# ESP32.net
KiCad netlist of a schematic drawn in Altium Designer
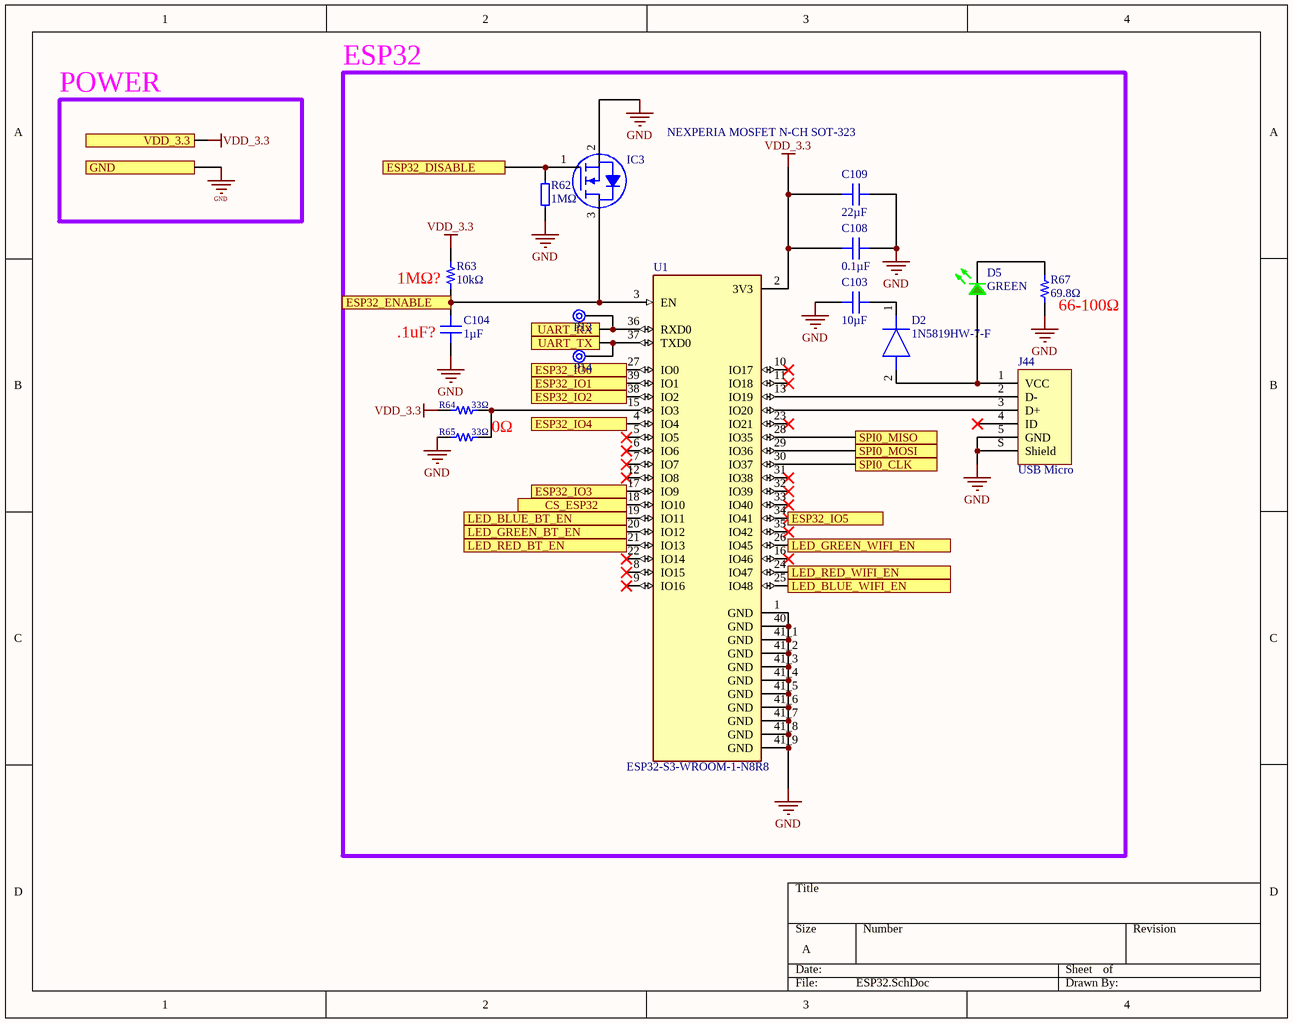
[diagram p0: ESP32.SchDoc]

(export (version "E")
  (design (tool "Eeschema 10.0.6"))
  (components
    (comp (ref "C103")
      (value "10µF")
      (footprint "CAP 0603_1608")
      (description "CAP CER 010UF 25V X7R 0603")
      (fields (field (name "MANUFACTURER") "KEMET") (field (name "VOLTAGE") "25V"))
      (libsource (lib "MVVVMAltiumDatabase") (part "Capacitor"))
    )
    (comp (ref "C104")
      (value "1µF")
      (footprint "CAP 0603_1608")
      (description "CAP CER 1UF 10V X7R 0603")
      (fields (field (name "MANUFACTURER") "KEMET") (field (name "VOLTAGE") "10V"))
      (libsource (lib "MVVVMAltiumDatabase") (part "Capacitor"))
    )
    (comp (ref "C108")
      (value "0.1µF")
      (footprint "CAP 0603_1608 RF")
      (description "CAP CER 0.1UF 16V X7R 0603")
      (fields (field (name "MANUFACTURER") "KEMET") (field (name "VOLTAGE") "16V"))
      (libsource (lib "MVVVMAltiumDatabase") (part "Capacitor"))
    )
    (comp (ref "C109")
      (value "22µF")
      (footprint "CAP 0805_2012")
      (description "CAP CER 22UF 10V X7R 0805")
      (fields (field (name "MANUFACTURER") "Murata Electronics") (field (name "VOLTAGE") "10V"))
      (libsource (lib "MVVVMAltiumDatabase") (part "Capacitor"))
    )
    (comp (ref "D2")
      (value "1N5819HW-7-F")
      (footprint "SamacSys:SOD3716X125N")
      (description "Diode")
      (libsource (lib "*") (part "1N5819HW-7-F"))
    )
    (comp (ref "D5")
      (value "GREEN")
      (footprint "LED 0603_1608")
      (description "LED RED CLEAR 0603 SMD")
      (fields (field (name "MANUFACTURER") "Würth Elektronik"))
      (libsource (lib "MVVVMAltiumDatabase") (part "LED_GREEN"))
    )
    (comp (ref "IC3")
      (value "NEXPERIA MOSFET N-CH SOT-323")
      (footprint "NEXPERIA SOT-323")
      (description "MOSFET N-CH 60V 320MA SOT323")
      (fields (field (name "MANUFACTURER") "Nexperia USA Inc."))
      (libsource (lib "MVVVMAltiumDatabase") (part "NEXPERIA MOSFET N-CH SOT-323"))
    )
    (comp (ref "J44")
      (value "USB Micro")
      (footprint "MICRO USB B")
      (fields (field (name "MANUFACTURER") "TE"))
      (libsource (lib "MVVVMAltiumDatabase") (part "USB 2.0 Type B Micro"))
    )
    (comp (ref "P13")
      (value "1 Pin")
      (footprint "1PINTHRU")
      (libsource (lib "MVVVMAltiumDatabase") (part "1 PIN THRU"))
    )
    (comp (ref "P14")
      (value "1 Pin")
      (footprint "1PINTHRU")
      (libsource (lib "MVVVMAltiumDatabase") (part "1 PIN THRU"))
    )
    (comp (ref "R62")
      (value "1MΩ")
      (footprint "0603_1608 RF")
      (description "0603 RF Passive")
      (libsource (lib "MVVVMAltiumDatabase") (part "RF Passive"))
    )
    (comp (ref "R63")
      (value "10kΩ")
      (footprint "RES 0603_1608 RF")
      (description "RES SMD 10K OHM 5% 1/10W 0603")
      (fields (field (name "MANUFACTURER") "Vishay Dale") (field (name "TOLERANCE") "±5%"))
      (libsource (lib "MVVVMAltiumDatabase") (part "Resistor"))
    )
    (comp (ref "R64")
      (value "33Ω")
      (footprint "RES 0201_0603")
      (description "RES SMD 33 OHM 1% 1/20W 0201")
      (fields (field (name "MANUFACTURER") "Vishay Dale") (field (name "TOLERANCE") "±1%"))
      (libsource (lib "MVVVMAltiumDatabase") (part "Resistor"))
    )
    (comp (ref "R65")
      (value "33Ω")
      (footprint "RES 0201_0603")
      (description "RES SMD 33 OHM 1% 1/20W 0201")
      (fields (field (name "MANUFACTURER") "Vishay Dale") (field (name "TOLERANCE") "±1%"))
      (libsource (lib "MVVVMAltiumDatabase") (part "Resistor"))
    )
    (comp (ref "R67")
      (value "69.8Ω")
      (footprint "RES 0603_1608 RF")
      (description "RES 69.8 OHM 1% 1/10W 0603")
      (fields (field (name "MANUFACTURER") "Vishay Dale") (field (name "TOLERANCE") "±1%"))
      (libsource (lib "MVVVMAltiumDatabase") (part "Resistor"))
    )
    (comp (ref "U1")
      (value "ESP32-S3-WROOM-1-N8R8")
      (footprint "XCVR_ESP32S3WROOM1N8R8")
      (description "Bluetooth, WiFi 802.11b/g/n, Bluetooth v5.0 Transceiver Module 2.4GHz PCB Trace Surface Mount")
      (fields (field (name "MF") "Espressif Systems"))
      (libsource (lib "ESP32-S3-WROOM-1-N8R8") (part "ESP32-S3-WROOM-1-N8R8"))
    )
  )
  (nets
    (net (code "1") (name "/CS_ESP32") (class "Default")
      (node (ref "U1") (pin "18") (pinfunction "IO10_18") (pintype "bidirectional"))
    )
    (net (code "2") (name "/ESP32_DISABLE") (class "Default")
      (node (ref "IC3") (pin "1") (pinfunction "G_1") (pintype "passive"))
      (node (ref "R62") (pin "1") (pinfunction "1_1") (pintype "passive"))
    )
    (net (code "3") (name "/ESP32_ENABLE") (class "Default")
      (node (ref "C104") (pin "2") (pinfunction "2_2") (pintype "passive"))
      (node (ref "IC3") (pin "3") (pinfunction "D_3") (pintype "passive"))
      (node (ref "R63") (pin "1") (pinfunction "1_1") (pintype "passive"))
      (node (ref "U1") (pin "3") (pinfunction "EN_3") (pintype "input"))
    )
    (net (code "4") (name "/ESP32_IO0") (class "Default")
      (node (ref "U1") (pin "27") (pinfunction "IO0_27") (pintype "bidirectional"))
    )
    (net (code "5") (name "/ESP32_IO1") (class "Default")
      (node (ref "U1") (pin "39") (pinfunction "IO1_39") (pintype "bidirectional"))
    )
    (net (code "6") (name "/ESP32_IO2") (class "Default")
      (node (ref "U1") (pin "38") (pinfunction "IO2_38") (pintype "bidirectional"))
    )
    (net (code "7") (name "/ESP32_IO3") (class "Default")
      (node (ref "U1") (pin "17") (pinfunction "IO9_17") (pintype "bidirectional"))
    )
    (net (code "8") (name "/ESP32_IO4") (class "Default")
      (node (ref "U1") (pin "4") (pinfunction "IO4_4") (pintype "bidirectional"))
    )
    (net (code "9") (name "/ESP32_IO5") (class "Default")
      (node (ref "U1") (pin "34") (pinfunction "IO41_34") (pintype "bidirectional+no_connect"))
    )
    (net (code "10") (name "/LED_BLUE_BT_EN") (class "Default")
      (node (ref "U1") (pin "19") (pinfunction "IO11_19") (pintype "bidirectional"))
    )
    (net (code "11") (name "/LED_BLUE_WIFI_EN") (class "Default")
      (node (ref "U1") (pin "25") (pinfunction "IO48_25") (pintype "bidirectional"))
    )
    (net (code "12") (name "/LED_GREEN_BT_EN") (class "Default")
      (node (ref "U1") (pin "20") (pinfunction "IO12_20") (pintype "bidirectional"))
    )
    (net (code "13") (name "/LED_GREEN_WIFI_EN") (class "Default")
      (node (ref "U1") (pin "26") (pinfunction "IO45_26") (pintype "bidirectional"))
    )
    (net (code "14") (name "/LED_RED_BT_EN") (class "Default")
      (node (ref "U1") (pin "21") (pinfunction "IO13_21") (pintype "bidirectional"))
    )
    (net (code "15") (name "/LED_RED_WIFI_EN") (class "Default")
      (node (ref "U1") (pin "24") (pinfunction "IO47_24") (pintype "bidirectional"))
    )
    (net (code "16") (name "/SPI0_CLK") (class "Default")
      (node (ref "U1") (pin "30") (pinfunction "IO37_30") (pintype "bidirectional"))
    )
    (net (code "17") (name "/SPI0_MISO") (class "Default")
      (node (ref "U1") (pin "28") (pinfunction "IO35_28") (pintype "bidirectional"))
    )
    (net (code "18") (name "/SPI0_MOSI") (class "Default")
      (node (ref "U1") (pin "29") (pinfunction "IO36_29") (pintype "bidirectional"))
    )
    (net (code "19") (name "/UART_RX") (class "Default")
      (node (ref "P13") (pin "1") (pinfunction "PAD_1") (pintype "passive"))
      (node (ref "U1") (pin "36") (pinfunction "RXD0_36") (pintype "bidirectional"))
    )
    (net (code "20") (name "/UART_TX") (class "Default")
      (node (ref "P14") (pin "1") (pinfunction "PAD_1") (pintype "passive"))
      (node (ref "U1") (pin "37") (pinfunction "TXD0_37") (pintype "bidirectional"))
    )
    (net (code "21") (name "GND") (class "Default")
      (node (ref "C103") (pin "1") (pinfunction "1_1") (pintype "passive"))
      (node (ref "C104") (pin "1") (pinfunction "1_1") (pintype "passive"))
      (node (ref "C108") (pin "1") (pinfunction "1_1") (pintype "passive"))
      (node (ref "C109") (pin "2") (pinfunction "2_2") (pintype "passive"))
      (node (ref "IC3") (pin "2") (pinfunction "S_2") (pintype "passive"))
      (node (ref "J44") (pin "5") (pinfunction "GND_5") (pintype "passive"))
      (node (ref "J44") (pin "S") (pinfunction "Shield_S") (pintype "passive"))
      (node (ref "R62") (pin "2") (pinfunction "2_2") (pintype "passive"))
      (node (ref "R65") (pin "1") (pinfunction "1_1") (pintype "passive"))
      (node (ref "R67") (pin "1") (pinfunction "1_1") (pintype "passive"))
      (node (ref "U1") (pin "1") (pinfunction "GND_1") (pintype "power_in"))
      (node (ref "U1") (pin "40") (pinfunction "GND_40") (pintype "power_in"))
      (node (ref "U1") (pin "41_1") (pinfunction "GND_41_1") (pintype "power_in"))
      (node (ref "U1") (pin "41_2") (pinfunction "GND_41_2") (pintype "power_in"))
      (node (ref "U1") (pin "41_3") (pinfunction "GND_41_3") (pintype "power_in"))
      (node (ref "U1") (pin "41_4") (pinfunction "GND_41_4") (pintype "power_in"))
      (node (ref "U1") (pin "41_5") (pinfunction "GND_41_5") (pintype "power_in"))
      (node (ref "U1") (pin "41_6") (pinfunction "GND_41_6") (pintype "power_in"))
      (node (ref "U1") (pin "41_7") (pinfunction "GND_41_7") (pintype "power_in"))
      (node (ref "U1") (pin "41_8") (pinfunction "GND_41_8") (pintype "power_in"))
      (node (ref "U1") (pin "41_9") (pinfunction "GND_41_9") (pintype "power_in"))
    )
    (net (code "22") (name "Net-(D2-A)") (class "Default")
      (node (ref "D2") (pin "2") (pinfunction "A_2") (pintype "passive"))
      (node (ref "D5") (pin "1") (pinfunction "1_1") (pintype "passive"))
      (node (ref "J44") (pin "1") (pinfunction "VCC_1") (pintype "passive"))
    )
    (net (code "23") (name "Net-(D2-K)") (class "Default")
      (node (ref "C103") (pin "2") (pinfunction "2_2") (pintype "passive"))
      (node (ref "D2") (pin "1") (pinfunction "K_1") (pintype "passive"))
    )
    (net (code "24") (name "Net-(D5-Pad2)") (class "Default")
      (node (ref "D5") (pin "2") (pinfunction "2_2") (pintype "passive"))
      (node (ref "R67") (pin "2") (pinfunction "2_2") (pintype "passive"))
    )
    (net (code "25") (name "Net-(J44-D+)") (class "Default")
      (node (ref "J44") (pin "3") (pinfunction "D+_3") (pintype "passive"))
      (node (ref "U1") (pin "14") (pinfunction "IO20_14") (pintype "bidirectional"))
    )
    (net (code "26") (name "Net-(J44-D-)") (class "Default")
      (node (ref "J44") (pin "2") (pinfunction "D-_2") (pintype "passive"))
      (node (ref "U1") (pin "13") (pinfunction "IO19_13") (pintype "bidirectional"))
    )
    (net (code "27") (name "Net-(U1-IO3)") (class "Default")
      (node (ref "R64") (pin "2") (pinfunction "2_2") (pintype "passive"))
      (node (ref "R65") (pin "2") (pinfunction "2_2") (pintype "passive"))
      (node (ref "U1") (pin "15") (pinfunction "IO3_15") (pintype "bidirectional"))
    )
    (net (code "28") (name "VDD_3.3") (class "Default")
      (node (ref "C108") (pin "2") (pinfunction "2_2") (pintype "passive"))
      (node (ref "C109") (pin "1") (pinfunction "1_1") (pintype "passive"))
      (node (ref "R63") (pin "2") (pinfunction "2_2") (pintype "passive"))
      (node (ref "R64") (pin "1") (pinfunction "1_1") (pintype "passive"))
      (node (ref "U1") (pin "2") (pinfunction "3V3_2") (pintype "power_in"))
    )
    (net (code "29") (name "unconnected-(J44-ID-Pad4)") (class "Default")
      (node (ref "J44") (pin "4") (pinfunction "ID_4") (pintype "passive+no_connect"))
    )
    (net (code "30") (name "unconnected-(U1-IO5-Pad5)") (class "Default")
      (node (ref "U1") (pin "5") (pinfunction "IO5_5") (pintype "bidirectional+no_connect"))
    )
    (net (code "31") (name "unconnected-(U1-IO6-Pad6)") (class "Default")
      (node (ref "U1") (pin "6") (pinfunction "IO6_6") (pintype "bidirectional+no_connect"))
    )
    (net (code "32") (name "unconnected-(U1-IO7-Pad7)") (class "Default")
      (node (ref "U1") (pin "7") (pinfunction "IO7_7") (pintype "bidirectional+no_connect"))
    )
    (net (code "33") (name "unconnected-(U1-IO8-Pad12)") (class "Default")
      (node (ref "U1") (pin "12") (pinfunction "IO8_12") (pintype "bidirectional+no_connect"))
    )
    (net (code "34") (name "unconnected-(U1-IO14-Pad22)") (class "Default")
      (node (ref "U1") (pin "22") (pinfunction "IO14_22") (pintype "bidirectional+no_connect"))
    )
    (net (code "35") (name "unconnected-(U1-IO15-Pad8)") (class "Default")
      (node (ref "U1") (pin "8") (pinfunction "IO15_8") (pintype "bidirectional+no_connect"))
    )
    (net (code "36") (name "unconnected-(U1-IO16-Pad9)") (class "Default")
      (node (ref "U1") (pin "9") (pinfunction "IO16_9") (pintype "bidirectional+no_connect"))
    )
    (net (code "37") (name "unconnected-(U1-IO17-Pad10)") (class "Default")
      (node (ref "U1") (pin "10") (pinfunction "IO17_10") (pintype "bidirectional+no_connect"))
    )
    (net (code "38") (name "unconnected-(U1-IO18-Pad11)") (class "Default")
      (node (ref "U1") (pin "11") (pinfunction "IO18_11") (pintype "bidirectional+no_connect"))
    )
    (net (code "39") (name "unconnected-(U1-IO21-Pad23)") (class "Default")
      (node (ref "U1") (pin "23") (pinfunction "IO21_23") (pintype "bidirectional+no_connect"))
    )
    (net (code "40") (name "unconnected-(U1-IO38-Pad31)") (class "Default")
      (node (ref "U1") (pin "31") (pinfunction "IO38_31") (pintype "bidirectional+no_connect"))
    )
    (net (code "41") (name "unconnected-(U1-IO39-Pad32)") (class "Default")
      (node (ref "U1") (pin "32") (pinfunction "IO39_32") (pintype "bidirectional+no_connect"))
    )
    (net (code "42") (name "unconnected-(U1-IO40-Pad33)") (class "Default")
      (node (ref "U1") (pin "33") (pinfunction "IO40_33") (pintype "bidirectional+no_connect"))
    )
    (net (code "43") (name "unconnected-(U1-IO42-Pad35)") (class "Default")
      (node (ref "U1") (pin "35") (pinfunction "IO42_35") (pintype "bidirectional+no_connect"))
    )
    (net (code "44") (name "unconnected-(U1-IO46-Pad16)") (class "Default")
      (node (ref "U1") (pin "16") (pinfunction "IO46_16") (pintype "bidirectional+no_connect"))
    )
  )
)
